# InputFilter.net
KiCad netlist of a schematic drawn in Altium Designer
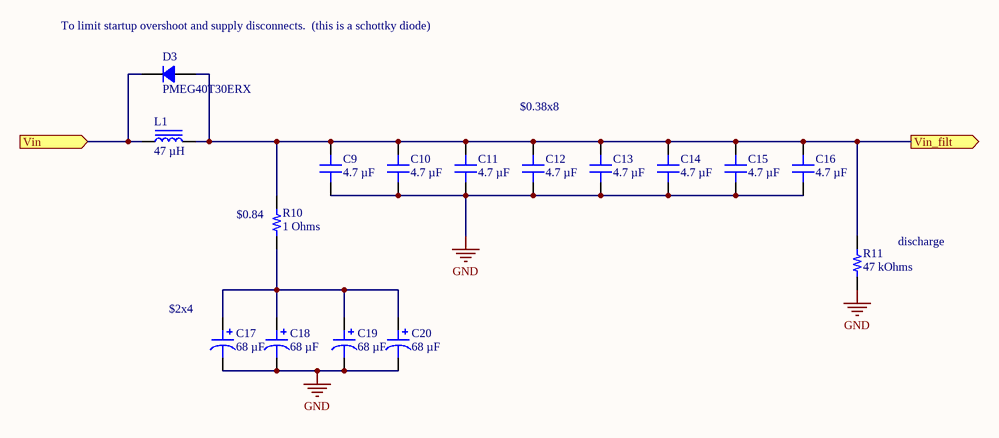
[diagram p0: InputFilter.SchDoc]

(export (version "E")
  (design (tool "Eeschema 10.0.6"))
  (components
    (comp (ref "C9")
      (value "4.7 µF")
      (footprint "CAP 1206_3216 - 0.8MM")
      (description "CAP CER 4.7UF 50V X7R 1206")
      (fields (field (name "PART NUMBER") "C1206C475K5RACTU") (field (name "MANUFACTURER") "KEMET"))
      (libsource (lib "Celestial Altium Library - altium_library") (part "Capacitor"))
    )
    (comp (ref "C10")
      (value "4.7 µF")
      (footprint "CAP 1206_3216 - 0.8MM")
      (description "CAP CER 4.7UF 50V X7R 1206")
      (fields (field (name "PART NUMBER") "C1206C475K5RACTU") (field (name "MANUFACTURER") "KEMET"))
      (libsource (lib "Celestial Altium Library - altium_library") (part "Capacitor"))
    )
    (comp (ref "C11")
      (value "4.7 µF")
      (footprint "CAP 1206_3216 - 0.8MM")
      (description "CAP CER 4.7UF 50V X7R 1206")
      (fields (field (name "PART NUMBER") "C1206C475K5RACTU") (field (name "MANUFACTURER") "KEMET"))
      (libsource (lib "Celestial Altium Library - altium_library") (part "Capacitor"))
    )
    (comp (ref "C12")
      (value "4.7 µF")
      (footprint "CAP 1206_3216 - 0.8MM")
      (description "CAP CER 4.7UF 50V X7R 1206")
      (fields (field (name "PART NUMBER") "C1206C475K5RACTU") (field (name "MANUFACTURER") "KEMET"))
      (libsource (lib "Celestial Altium Library - altium_library") (part "Capacitor"))
    )
    (comp (ref "C13")
      (value "4.7 µF")
      (footprint "CAP 1206_3216 - 0.8MM")
      (description "CAP CER 4.7UF 50V X7R 1206")
      (fields (field (name "PART NUMBER") "C1206C475K5RACTU") (field (name "MANUFACTURER") "KEMET"))
      (libsource (lib "Celestial Altium Library - altium_library") (part "Capacitor"))
    )
    (comp (ref "C14")
      (value "4.7 µF")
      (footprint "CAP 1206_3216 - 0.8MM")
      (description "CAP CER 4.7UF 50V X7R 1206")
      (fields (field (name "PART NUMBER") "C1206C475K5RACTU") (field (name "MANUFACTURER") "KEMET"))
      (libsource (lib "Celestial Altium Library - altium_library") (part "Capacitor"))
    )
    (comp (ref "C15")
      (value "4.7 µF")
      (footprint "CAP 1206_3216 - 0.8MM")
      (description "CAP CER 4.7UF 50V X7R 1206")
      (fields (field (name "PART NUMBER") "C1206C475K5RACTU") (field (name "MANUFACTURER") "KEMET"))
      (libsource (lib "Celestial Altium Library - altium_library") (part "Capacitor"))
    )
    (comp (ref "C16")
      (value "4.7 µF")
      (footprint "CAP 1206_3216 - 0.8MM")
      (description "CAP CER 4.7UF 50V X7R 1206")
      (fields (field (name "PART NUMBER") "C1206C475K5RACTU") (field (name "MANUFACTURER") "KEMET"))
      (libsource (lib "Celestial Altium Library - altium_library") (part "Capacitor"))
    )
    (comp (ref "C17")
      (value "68 µF")
      (footprint "CAP POL 2917_7343")
      (description "CAP TANT 68UF 10% 25V 2917")
      (fields (field (name "PART NUMBER") "T491X686K025AT") (field (name "MANUFACTURER") "KEMET"))
      (libsource (lib "Celestial Altium Library - altium_library") (part "Polarised Capacitor"))
    )
    (comp (ref "C18")
      (value "68 µF")
      (footprint "CAP POL 2917_7343")
      (description "CAP TANT 68UF 10% 25V 2917")
      (fields (field (name "PART NUMBER") "T491X686K025AT") (field (name "MANUFACTURER") "KEMET"))
      (libsource (lib "Celestial Altium Library - altium_library") (part "Polarised Capacitor"))
    )
    (comp (ref "C19")
      (value "68 µF")
      (footprint "CAP POL 2917_7343")
      (description "CAP TANT 68UF 10% 25V 2917")
      (fields (field (name "PART NUMBER") "T491X686K025AT") (field (name "MANUFACTURER") "KEMET"))
      (libsource (lib "Celestial Altium Library - altium_library") (part "Polarised Capacitor"))
    )
    (comp (ref "C20")
      (value "68 µF")
      (footprint "CAP POL 2917_7343")
      (description "CAP TANT 68UF 10% 25V 2917")
      (fields (field (name "PART NUMBER") "T491X686K025AT") (field (name "MANUFACTURER") "KEMET"))
      (libsource (lib "Celestial Altium Library - altium_library") (part "Polarised Capacitor"))
    )
    (comp (ref "D3")
      (value "PMEG40T30ERX")
      (footprint "SOD-123W")
      (description "DIODE SCHOTTKY 40V 3A SOD123W")
      (fields (field (name "MANUFACTURER") "Nexperia USA Inc."))
      (libsource (lib "Celestial Altium Library - altium_library") (part "Diode"))
    )
    (comp (ref "L1")
      (value "47 µH")
      (footprint "WURTH WE-HCF 14.5MM")
      (description "FIXED IND 47UH 12A 12.2 MOHM SMD")
      (fields (field (name "PART NUMBER") "7443634700") (field (name "MANUFACTURER") "Würth Elektronik"))
      (libsource (lib "Celestial Altium Library - altium_library") (part "Inductor"))
    )
    (comp (ref "R10")
      (value "1 Ohms")
      (footprint "RES 2512_6432")
      (description "RES 1 OHM 1% 2W 2512")
      (fields
        (field (name "PART NUMBER") "RHC2512FT1R00")
        (field (name "MANUFACTURER") "Stackpole Electronics Inc")
      )
      (libsource (lib "Celestial Altium Library - altium_library") (part "Resistor"))
    )
    (comp (ref "R11")
      (value "47 kOhms")
      (footprint "RES 1206_3216")
      (description "RES SMD 47K OHM 1% 1/4W 1206")
      (fields (field (name "PART NUMBER") "CRCW120647K0FKEA") (field (name "MANUFACTURER") "Vishay Dale"))
      (libsource (lib "Celestial Altium Library - altium_library") (part "Resistor"))
    )
  )
  (nets
    (net (code "1") (name "/Vin") (class "Default")
      (node (ref "D3") (pin "2") (pinfunction "2_2") (pintype "passive"))
      (node (ref "L1") (pin "2") (pinfunction "2_2") (pintype "passive"))
    )
    (net (code "2") (name "/Vin_filt") (class "Default")
      (node (ref "C10") (pin "2") (pinfunction "2_2") (pintype "passive"))
      (node (ref "C11") (pin "2") (pinfunction "2_2") (pintype "passive"))
      (node (ref "C12") (pin "2") (pinfunction "2_2") (pintype "passive"))
      (node (ref "C13") (pin "2") (pinfunction "2_2") (pintype "passive"))
      (node (ref "C14") (pin "2") (pinfunction "2_2") (pintype "passive"))
      (node (ref "C15") (pin "2") (pinfunction "2_2") (pintype "passive"))
      (node (ref "C16") (pin "2") (pinfunction "2_2") (pintype "passive"))
      (node (ref "C9") (pin "2") (pinfunction "2_2") (pintype "passive"))
      (node (ref "D3") (pin "1") (pinfunction "1_1") (pintype "passive"))
      (node (ref "L1") (pin "1") (pinfunction "1_1") (pintype "passive"))
      (node (ref "R10") (pin "2") (pinfunction "2_2") (pintype "passive"))
      (node (ref "R11") (pin "2") (pinfunction "2_2") (pintype "passive"))
    )
    (net (code "3") (name "GND") (class "Default")
      (node (ref "C10") (pin "1") (pinfunction "1_1") (pintype "passive"))
      (node (ref "C11") (pin "1") (pinfunction "1_1") (pintype "passive"))
      (node (ref "C12") (pin "1") (pinfunction "1_1") (pintype "passive"))
      (node (ref "C13") (pin "1") (pinfunction "1_1") (pintype "passive"))
      (node (ref "C14") (pin "1") (pinfunction "1_1") (pintype "passive"))
      (node (ref "C15") (pin "1") (pinfunction "1_1") (pintype "passive"))
      (node (ref "C16") (pin "1") (pinfunction "1_1") (pintype "passive"))
      (node (ref "C17") (pin "2") (pinfunction "2_2") (pintype "passive"))
      (node (ref "C18") (pin "2") (pinfunction "2_2") (pintype "passive"))
      (node (ref "C19") (pin "2") (pinfunction "2_2") (pintype "passive"))
      (node (ref "C20") (pin "2") (pinfunction "2_2") (pintype "passive"))
      (node (ref "C9") (pin "1") (pinfunction "1_1") (pintype "passive"))
      (node (ref "R11") (pin "1") (pinfunction "1_1") (pintype "passive"))
    )
    (net (code "4") (name "Net-(C17-Pad1)") (class "Default")
      (node (ref "C17") (pin "1") (pinfunction "1_1") (pintype "passive"))
      (node (ref "C18") (pin "1") (pinfunction "1_1") (pintype "passive"))
      (node (ref "C19") (pin "1") (pinfunction "1_1") (pintype "passive"))
      (node (ref "C20") (pin "1") (pinfunction "1_1") (pintype "passive"))
      (node (ref "R10") (pin "1") (pinfunction "1_1") (pintype "passive"))
    )
  )
)
